# Sheet1.net
KiCad netlist of a schematic drawn in Altium Designer
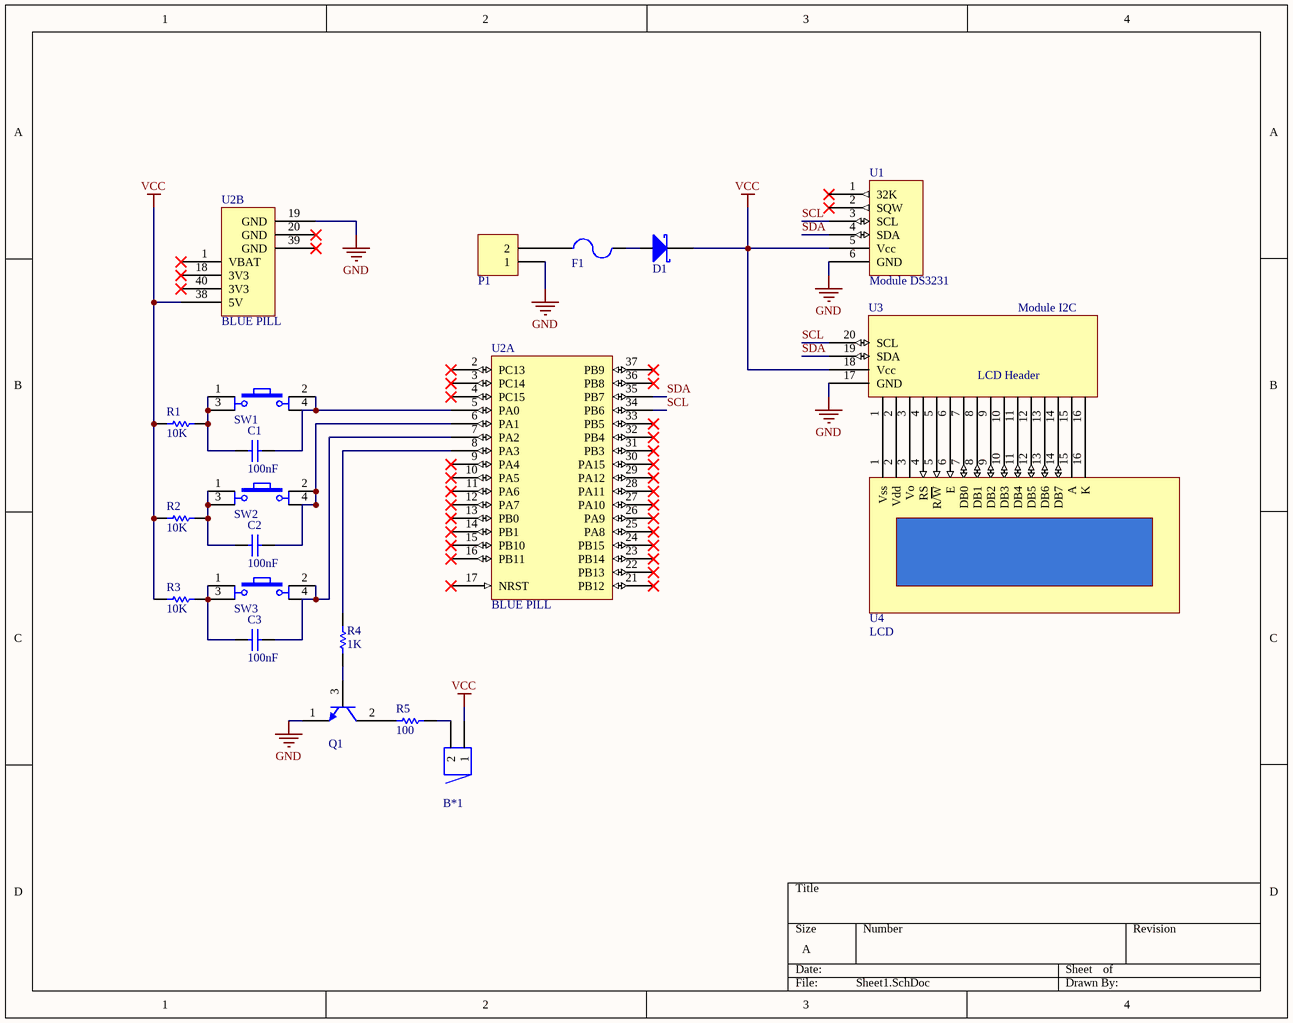
[diagram p0: Sheet1.SchDoc]

(export (version "E")
  (design (tool "Eeschema 10.0.6"))
  (components
    (comp (ref "B*1") (value "Buzzer") (footprint "BUZZER") (libsource (lib "PIF_Library") (part "Buzzer")))
    (comp (ref "C1")
      (value "100nF")
      (footprint "CAP-SM-0805")
      (description "Capacitor")
      (fields (field (name "Comment") "Cap Non-Pol SMD"))
      (libsource (lib "PIF_Library") (part "Cap Non-Pol SMD"))
    )
    (comp (ref "C2")
      (value "100nF")
      (footprint "CAP-SM-0805")
      (description "Capacitor")
      (fields (field (name "Comment") "Cap Non-Pol SMD"))
      (libsource (lib "PIF_Library") (part "Cap Non-Pol SMD"))
    )
    (comp (ref "C3")
      (value "100nF")
      (footprint "CAP-SM-0805")
      (description "Capacitor")
      (fields (field (name "Comment") "Cap Non-Pol SMD"))
      (libsource (lib "PIF_Library") (part "Cap Non-Pol SMD"))
    )
    (comp (ref "D1")
      (value "D Schottky")
      (footprint "SS34")
      (description "Schottky Diode")
      (fields (field (name "PUBLISHER") "Altium Limited"))
      (libsource (lib "PIF_Library") (part "D Schottky"))
    )
    (comp (ref "F1") (value "Fuse") (footprint "FUSE SMD") (libsource (lib "PIF_Library") (part "Fuse")))
    (comp (ref "P1")
      (value "Domino 2")
      (footprint "DOMINO 2- 5mm")
      (description "Domino, 2-Pin")
      (fields (field (name "PUBLISHER") "Altium Limited"))
      (libsource (lib "PIF_Library") (part "Domino 2"))
    )
    (comp (ref "Q1")
      (value "C1815")
      (footprint "QTO-92")
      (description "NPN Bipolar Transistor")
      (libsource (lib "PIF_Library") (part "C1815"))
    )
    (comp (ref "R1")
      (value "10K")
      (footprint "RES-SM-0805")
      (description "Resistor")
      (fields (field (name "Comment") "RESISTOR SMD"))
      (libsource (lib "PIF_Library") (part "RESISTOR SMD"))
    )
    (comp (ref "R2")
      (value "10K")
      (footprint "RES-SM-0805")
      (description "Resistor")
      (fields (field (name "Comment") "RESISTOR SMD"))
      (libsource (lib "PIF_Library") (part "RESISTOR SMD"))
    )
    (comp (ref "R3")
      (value "10K")
      (footprint "RES-SM-0805")
      (description "Resistor")
      (fields (field (name "Comment") "RESISTOR SMD"))
      (libsource (lib "PIF_Library") (part "RESISTOR SMD"))
    )
    (comp (ref "R4")
      (value "1K")
      (footprint "RES-SM-0603")
      (description "Resistor")
      (fields (field (name "Comment") "RESISTOR SMD"))
      (libsource (lib "PIF_Library") (part "RESISTOR SMD"))
    )
    (comp (ref "R5")
      (value "100")
      (footprint "RES-SM-0603")
      (description "Resistor")
      (fields (field (name "Comment") "RESISTOR SMD"))
      (libsource (lib "PIF_Library") (part "RESISTOR SMD"))
    )
    (comp (ref "SW1")
      (value "SW")
      (footprint "Tact SW 4 pin")
      (description "Switch button 4 pin")
      (libsource (lib "PIF_Library") (part "Tact SW - 4Pin"))
    )
    (comp (ref "SW2")
      (value "SW")
      (footprint "Tact SW 4 pin")
      (description "Switch button 4 pin")
      (libsource (lib "PIF_Library") (part "Tact SW - 4Pin"))
    )
    (comp (ref "SW3")
      (value "SW")
      (footprint "Tact SW 4 pin")
      (description "Switch button 4 pin")
      (libsource (lib "PIF_Library") (part "Tact SW - 4Pin"))
    )
    (comp (ref "U1")
      (value "Module DS3231")
      (footprint "MODULE DS3231( Part B )")
      (libsource (lib "230215_PIFProject_LibPCB_Tvy_v") (part "DS3231"))
    )
    (comp (ref "U2")
      (value "BLUE PILL")
      (footprint "STM32F103C8T6")
      (libsource (lib "230215_PIFProject_LibPCB_Tvy_v") (part "STM32F103C8T6"))
    )
    (comp (ref "U3")
      (value "Module I2C")
      (footprint "Module I2C")
      (description "I2C converter circuit for LCD")
      (fields (field (name "MANUFACTURER") "Mantech"))
      (libsource (lib "230215_PIFProject_LibPCB_Tvy_v") (part "I2C interface for LCD"))
    )
    (comp (ref "U4")
      (value "LCD")
      (footprint "LCD1602")
      (fields (field (name "MANUFACTURER") "411 Technology systems"))
      (libsource (lib "230215_PIFProject_LibPCB_Tvy_v") (part "LCD1602"))
    )
  )
  (nets
    (net (code "1") (name "/SCL") (class "Default")
      (node (ref "U1") (pin "3") (pinfunction "SCL_3") (pintype "bidirectional"))
      (node (ref "U2") (pin "34") (pinfunction "PB6_34") (pintype "bidirectional"))
      (node (ref "U3") (pin "20") (pinfunction "SCL_20") (pintype "bidirectional"))
    )
    (net (code "2") (name "/SDA") (class "Default")
      (node (ref "U1") (pin "4") (pinfunction "SDA_4") (pintype "bidirectional"))
      (node (ref "U2") (pin "35") (pinfunction "PB7_35") (pintype "bidirectional"))
      (node (ref "U3") (pin "19") (pinfunction "SDA_19") (pintype "bidirectional"))
    )
    (net (code "3") (name "GND") (class "Default")
      (node (ref "P1") (pin "1") (pinfunction "1_1") (pintype "passive"))
      (node (ref "Q1") (pin "1") (pinfunction "E_1") (pintype "passive"))
      (node (ref "U1") (pin "6") (pinfunction "GND_6") (pintype "power_in"))
      (node (ref "U2") (pin "19") (pinfunction "GND_19") (pintype "power_in"))
      (node (ref "U3") (pin "17") (pinfunction "GND_17") (pintype "power_in"))
    )
    (net (code "4") (name "Net-(B*1-Pad2)") (class "Default")
      (node (ref "B*1") (pin "2") (pinfunction "2_2") (pintype "passive"))
      (node (ref "R5") (pin "2") (pinfunction "2_2") (pintype "passive"))
    )
    (net (code "5") (name "Net-(C1-Pad1)") (class "Default")
      (node (ref "C1") (pin "1") (pinfunction "1_1") (pintype "passive"))
      (node (ref "R1") (pin "2") (pinfunction "2_2") (pintype "passive"))
      (node (ref "SW1") (pin "1") (pintype "passive"))
      (node (ref "SW1") (pin "3") (pintype "passive"))
    )
    (net (code "6") (name "Net-(C2-Pad1)") (class "Default")
      (node (ref "C2") (pin "1") (pinfunction "1_1") (pintype "passive"))
      (node (ref "R2") (pin "2") (pinfunction "2_2") (pintype "passive"))
      (node (ref "SW2") (pin "1") (pintype "passive"))
      (node (ref "SW2") (pin "3") (pintype "passive"))
    )
    (net (code "7") (name "Net-(C3-Pad1)") (class "Default")
      (node (ref "C3") (pin "1") (pinfunction "1_1") (pintype "passive"))
      (node (ref "R3") (pin "2") (pinfunction "2_2") (pintype "passive"))
      (node (ref "SW3") (pin "1") (pintype "passive"))
      (node (ref "SW3") (pin "3") (pintype "passive"))
    )
    (net (code "8") (name "Net-(D1-A)") (class "Default")
      (node (ref "D1") (pin "1") (pinfunction "A_1") (pintype "passive"))
      (node (ref "F1") (pin "2") (pinfunction "2_2") (pintype "passive"))
    )
    (net (code "9") (name "Net-(F1-Pad1)") (class "Default")
      (node (ref "F1") (pin "1") (pinfunction "1_1") (pintype "passive"))
      (node (ref "P1") (pin "2") (pinfunction "2_2") (pintype "passive"))
    )
    (net (code "10") (name "Net-(Q1-B)") (class "Default")
      (node (ref "Q1") (pin "3") (pinfunction "B_3") (pintype "passive"))
      (node (ref "R4") (pin "1") (pinfunction "1_1") (pintype "passive"))
    )
    (net (code "11") (name "Net-(Q1-C)") (class "Default")
      (node (ref "Q1") (pin "2") (pinfunction "C_2") (pintype "passive"))
      (node (ref "R5") (pin "1") (pinfunction "1_1") (pintype "passive"))
    )
    (net (code "12") (name "Net-(U2A-PA0)") (class "Default")
      (node (ref "C1") (pin "2") (pinfunction "2_2") (pintype "passive"))
      (node (ref "SW1") (pin "2") (pintype "passive"))
      (node (ref "SW1") (pin "4") (pintype "passive"))
      (node (ref "U2") (pin "5") (pinfunction "PA0_5") (pintype "bidirectional"))
    )
    (net (code "13") (name "Net-(U2A-PA1)") (class "Default")
      (node (ref "C2") (pin "2") (pinfunction "2_2") (pintype "passive"))
      (node (ref "SW2") (pin "2") (pintype "passive"))
      (node (ref "SW2") (pin "4") (pintype "passive"))
      (node (ref "U2") (pin "6") (pinfunction "PA1_6") (pintype "bidirectional"))
    )
    (net (code "14") (name "Net-(U2A-PA2)") (class "Default")
      (node (ref "C3") (pin "2") (pinfunction "2_2") (pintype "passive"))
      (node (ref "SW3") (pin "2") (pintype "passive"))
      (node (ref "SW3") (pin "4") (pintype "passive"))
      (node (ref "U2") (pin "7") (pinfunction "PA2_7") (pintype "bidirectional"))
    )
    (net (code "15") (name "Net-(U2A-PA3)") (class "Default")
      (node (ref "R4") (pin "2") (pinfunction "2_2") (pintype "passive"))
      (node (ref "U2") (pin "8") (pinfunction "PA3_8") (pintype "bidirectional"))
    )
    (net (code "16") (name "Net-(U3-LCD_header_1)") (class "Default")
      (node (ref "U3") (pin "1") (pinfunction "LCD_header_1_1") (pintype "passive"))
      (node (ref "U4") (pin "1") (pinfunction "Vss_1") (pintype "power_in"))
    )
    (net (code "17") (name "Net-(U3-LCD_header_2)") (class "Default")
      (node (ref "U3") (pin "2") (pinfunction "LCD_header_2_2") (pintype "passive"))
      (node (ref "U4") (pin "2") (pinfunction "Vdd_2") (pintype "power_in"))
    )
    (net (code "18") (name "Net-(U3-LCD_header_3)") (class "Default")
      (node (ref "U3") (pin "3") (pinfunction "LCD_header_3_3") (pintype "passive"))
      (node (ref "U4") (pin "3") (pinfunction "Vo_3") (pintype "power_in"))
    )
    (net (code "19") (name "Net-(U3-LCD_header_4)") (class "Default")
      (node (ref "U3") (pin "4") (pinfunction "LCD_header_4_4") (pintype "passive"))
      (node (ref "U4") (pin "4") (pinfunction "RS_4") (pintype "input"))
    )
    (net (code "20") (name "Net-(U3-LCD_header_5)") (class "Default")
      (node (ref "U3") (pin "5") (pinfunction "LCD_header_5_5") (pintype "passive"))
      (node (ref "U4") (pin "5") (pinfunction "R/W_5") (pintype "input"))
    )
    (net (code "21") (name "Net-(U3-LCD_header_7)") (class "Default")
      (node (ref "U3") (pin "7") (pinfunction "LCD_header_7_7") (pintype "passive"))
      (node (ref "U4") (pin "7") (pinfunction "DB0_7") (pintype "bidirectional"))
    )
    (net (code "22") (name "Net-(U3-LCD_header_8)") (class "Default")
      (node (ref "U3") (pin "8") (pinfunction "LCD_header_8_8") (pintype "passive"))
      (node (ref "U4") (pin "8") (pinfunction "DB1_8") (pintype "bidirectional"))
    )
    (net (code "23") (name "Net-(U3-LCD_header_9)") (class "Default")
      (node (ref "U3") (pin "9") (pinfunction "LCD_header_9_9") (pintype "passive"))
      (node (ref "U4") (pin "9") (pinfunction "DB2_9") (pintype "bidirectional"))
    )
    (net (code "24") (name "Net-(U3-LCD_header_10)") (class "Default")
      (node (ref "U3") (pin "10") (pinfunction "LCD_header_10_10") (pintype "passive"))
      (node (ref "U4") (pin "10") (pinfunction "DB3_10") (pintype "bidirectional"))
    )
    (net (code "25") (name "Net-(U3-LCD_header_11)") (class "Default")
      (node (ref "U3") (pin "11") (pinfunction "LCD_header_11_11") (pintype "passive"))
      (node (ref "U4") (pin "11") (pinfunction "DB4_11") (pintype "bidirectional"))
    )
    (net (code "26") (name "Net-(U3-LCD_header_12)") (class "Default")
      (node (ref "U3") (pin "12") (pinfunction "LCD_header_12_12") (pintype "passive"))
      (node (ref "U4") (pin "12") (pinfunction "DB5_12") (pintype "bidirectional"))
    )
    (net (code "27") (name "Net-(U3-LCD_header_13)") (class "Default")
      (node (ref "U3") (pin "13") (pinfunction "LCD_header_13_13") (pintype "passive"))
      (node (ref "U4") (pin "13") (pinfunction "DB6_13") (pintype "bidirectional"))
    )
    (net (code "28") (name "Net-(U3-LCD_header_14)") (class "Default")
      (node (ref "U3") (pin "14") (pinfunction "LCD_header_14_14") (pintype "passive"))
      (node (ref "U4") (pin "14") (pinfunction "DB7_14") (pintype "bidirectional"))
    )
    (net (code "29") (name "Net-(U3-LCD_header_15)") (class "Default")
      (node (ref "U3") (pin "15") (pinfunction "LCD_header_15_15") (pintype "passive"))
      (node (ref "U4") (pin "15") (pinfunction "A_15") (pintype "passive"))
    )
    (net (code "30") (name "Net-(U3-LCD_header_16)") (class "Default")
      (node (ref "U3") (pin "16") (pinfunction "LCD_header_16_16") (pintype "passive"))
      (node (ref "U4") (pin "16") (pinfunction "K_16") (pintype "passive"))
    )
    (net (code "31") (name "Net-(U4-E)") (class "Default")
      (node (ref "U3") (pin "6") (pinfunction "6_6") (pintype "passive"))
      (node (ref "U4") (pin "6") (pinfunction "E_6") (pintype "input"))
    )
    (net (code "32") (name "VCC") (class "Default")
      (node (ref "B*1") (pin "1") (pinfunction "1_1") (pintype "passive"))
      (node (ref "D1") (pin "2") (pinfunction "K_2") (pintype "passive"))
      (node (ref "R1") (pin "1") (pinfunction "1_1") (pintype "passive"))
      (node (ref "R2") (pin "1") (pinfunction "1_1") (pintype "passive"))
      (node (ref "R3") (pin "1") (pinfunction "1_1") (pintype "passive"))
      (node (ref "U1") (pin "5") (pinfunction "Vcc_5") (pintype "power_in"))
      (node (ref "U2") (pin "38") (pinfunction "5V_38") (pintype "power_in"))
      (node (ref "U3") (pin "18") (pinfunction "Vcc_18") (pintype "power_in"))
    )
    (net (code "33") (name "unconnected-(U1-32K-Pad1)") (class "Default")
      (node (ref "U1") (pin "1") (pinfunction "32K_1") (pintype "output+no_connect"))
    )
    (net (code "34") (name "unconnected-(U1-SQW-Pad2)") (class "Default")
      (node (ref "U1") (pin "2") (pinfunction "SQW_2") (pintype "output+no_connect"))
    )
    (net (code "35") (name "unconnected-(U2A-NRST-Pad17)") (class "Default")
      (node (ref "U2") (pin "17") (pinfunction "NRST_17") (pintype "input+no_connect"))
    )
    (net (code "36") (name "unconnected-(U2A-PA4-Pad9)") (class "Default")
      (node (ref "U2") (pin "9") (pinfunction "PA4_9") (pintype "bidirectional+no_connect"))
    )
    (net (code "37") (name "unconnected-(U2A-PA5-Pad10)") (class "Default")
      (node (ref "U2") (pin "10") (pinfunction "PA5_10") (pintype "bidirectional+no_connect"))
    )
    (net (code "38") (name "unconnected-(U2A-PA6-Pad11)") (class "Default")
      (node (ref "U2") (pin "11") (pinfunction "PA6_11") (pintype "bidirectional+no_connect"))
    )
    (net (code "39") (name "unconnected-(U2A-PA7-Pad12)") (class "Default")
      (node (ref "U2") (pin "12") (pinfunction "PA7_12") (pintype "bidirectional+no_connect"))
    )
    (net (code "40") (name "unconnected-(U2A-PA8-Pad25)") (class "Default")
      (node (ref "U2") (pin "25") (pinfunction "PA8_25") (pintype "bidirectional+no_connect"))
    )
    (net (code "41") (name "unconnected-(U2A-PA9-Pad26)") (class "Default")
      (node (ref "U2") (pin "26") (pinfunction "PA9_26") (pintype "bidirectional+no_connect"))
    )
    (net (code "42") (name "unconnected-(U2A-PA10-Pad27)") (class "Default")
      (node (ref "U2") (pin "27") (pinfunction "PA10_27") (pintype "bidirectional+no_connect"))
    )
    (net (code "43") (name "unconnected-(U2A-PA11-Pad28)") (class "Default")
      (node (ref "U2") (pin "28") (pinfunction "PA11_28") (pintype "bidirectional+no_connect"))
    )
    (net (code "44") (name "unconnected-(U2A-PA12-Pad29)") (class "Default")
      (node (ref "U2") (pin "29") (pinfunction "PA12_29") (pintype "bidirectional+no_connect"))
    )
    (net (code "45") (name "unconnected-(U2A-PA15-Pad30)") (class "Default")
      (node (ref "U2") (pin "30") (pinfunction "PA15_30") (pintype "bidirectional+no_connect"))
    )
    (net (code "46") (name "unconnected-(U2A-PB0-Pad13)") (class "Default")
      (node (ref "U2") (pin "13") (pinfunction "PB0_13") (pintype "bidirectional+no_connect"))
    )
    (net (code "47") (name "unconnected-(U2A-PB1-Pad14)") (class "Default")
      (node (ref "U2") (pin "14") (pinfunction "PB1_14") (pintype "bidirectional+no_connect"))
    )
    (net (code "48") (name "unconnected-(U2A-PB3-Pad31)") (class "Default")
      (node (ref "U2") (pin "31") (pinfunction "PB3_31") (pintype "bidirectional+no_connect"))
    )
    (net (code "49") (name "unconnected-(U2A-PB4-Pad32)") (class "Default")
      (node (ref "U2") (pin "32") (pinfunction "PB4_32") (pintype "bidirectional+no_connect"))
    )
    (net (code "50") (name "unconnected-(U2A-PB5-Pad33)") (class "Default")
      (node (ref "U2") (pin "33") (pinfunction "PB5_33") (pintype "bidirectional+no_connect"))
    )
    (net (code "51") (name "unconnected-(U2A-PB8-Pad36)") (class "Default")
      (node (ref "U2") (pin "36") (pinfunction "PB8_36") (pintype "bidirectional+no_connect"))
    )
    (net (code "52") (name "unconnected-(U2A-PB9-Pad37)") (class "Default")
      (node (ref "U2") (pin "37") (pinfunction "PB9_37") (pintype "bidirectional+no_connect"))
    )
    (net (code "53") (name "unconnected-(U2A-PB10-Pad15)") (class "Default")
      (node (ref "U2") (pin "15") (pinfunction "PB10_15") (pintype "bidirectional+no_connect"))
    )
    (net (code "54") (name "unconnected-(U2A-PB11-Pad16)") (class "Default")
      (node (ref "U2") (pin "16") (pinfunction "PB11_16") (pintype "bidirectional+no_connect"))
    )
    (net (code "55") (name "unconnected-(U2A-PB12-Pad21)") (class "Default")
      (node (ref "U2") (pin "21") (pinfunction "PB12_21") (pintype "bidirectional+no_connect"))
    )
    (net (code "56") (name "unconnected-(U2A-PB13-Pad22)") (class "Default")
      (node (ref "U2") (pin "22") (pinfunction "PB13_22") (pintype "bidirectional+no_connect"))
    )
    (net (code "57") (name "unconnected-(U2A-PB14-Pad23)") (class "Default")
      (node (ref "U2") (pin "23") (pinfunction "PB14_23") (pintype "bidirectional+no_connect"))
    )
    (net (code "58") (name "unconnected-(U2A-PB15-Pad24)") (class "Default")
      (node (ref "U2") (pin "24") (pinfunction "PB15_24") (pintype "bidirectional+no_connect"))
    )
    (net (code "59") (name "unconnected-(U2A-PC13-Pad2)") (class "Default")
      (node (ref "U2") (pin "2") (pinfunction "PC13_2") (pintype "bidirectional+no_connect"))
    )
    (net (code "60") (name "unconnected-(U2A-PC14-Pad3)") (class "Default")
      (node (ref "U2") (pin "3") (pinfunction "PC14_3") (pintype "bidirectional+no_connect"))
    )
    (net (code "61") (name "unconnected-(U2A-PC15-Pad4)") (class "Default")
      (node (ref "U2") (pin "4") (pinfunction "PC15_4") (pintype "bidirectional+no_connect"))
    )
    (net (code "62") (name "unconnected-(U2B-3V3-Pad18)") (class "Default")
      (node (ref "U2") (pin "18") (pinfunction "3V3_18") (pintype "power_in+no_connect"))
    )
    (net (code "63") (name "unconnected-(U2B-3V3-Pad40)") (class "Default")
      (node (ref "U2") (pin "40") (pinfunction "3V3_40") (pintype "power_in+no_connect"))
    )
    (net (code "64") (name "unconnected-(U2B-GND-Pad20)") (class "Default")
      (node (ref "U2") (pin "20") (pinfunction "GND_20") (pintype "power_in+no_connect"))
    )
    (net (code "65") (name "unconnected-(U2B-GND-Pad39)") (class "Default")
      (node (ref "U2") (pin "39") (pinfunction "GND_39") (pintype "power_in+no_connect"))
    )
    (net (code "66") (name "unconnected-(U2B-VBAT-Pad1)") (class "Default")
      (node (ref "U2") (pin "1") (pinfunction "VBAT_1") (pintype "power_in+no_connect"))
    )
  )
)
